# 5VDC_Supply.net
KiCad netlist of a schematic drawn in EAGLE
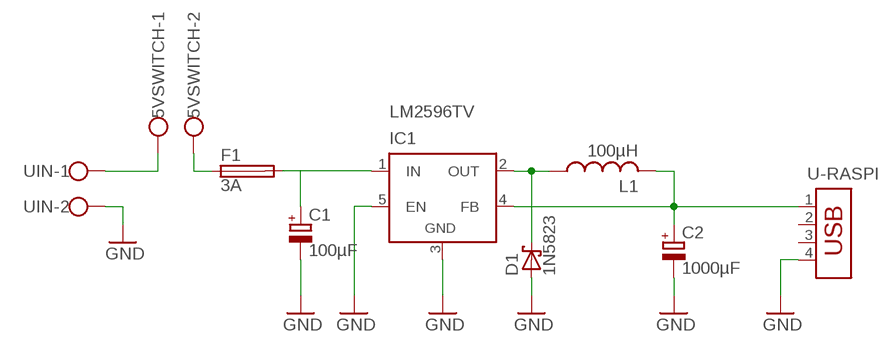
[diagram p0: schematic, sheet 1]

(export (version "E")
  (design (tool "Eeschema 10.0.6"))
  (components
    (comp (ref "5VSWITCH")
      (value "W237-102")
      (footprint "eagle-import:W237-102")
      (fields (field (name "MPN") "237-102"))
      (libsource (lib "eagle-import") (part "W237-102"))
    )
    (comp (ref "C1")
      (value "100µF")
      (footprint "eagle-import:E5-6")
      (libsource (lib "eagle-import") (part "CPOL-EUE5-6"))
    )
    (comp (ref "C2")
      (value "1000µF")
      (footprint "eagle-import:E5-10,5")
      (libsource (lib "eagle-import") (part "CPOL-EUE5-10.5"))
    )
    (comp (ref "D1")
      (value "1N5823")
      (footprint "eagle-import:C4111-15")
      (libsource (lib "eagle-import") (part "1N5908"))
    )
    (comp (ref "F1")
      (value "3A")
      (footprint "eagle-import:GSH15")
      (fields (field (name "MPN") "64900001039"))
      (libsource (lib "eagle-import") (part "GSH15"))
    )
    (comp (ref "IC1")
      (value "LM2596TV")
      (footprint "eagle-import:TO220-51")
      (libsource (lib "eagle-import") (part "LM2596TV"))
    )
    (comp (ref "L1")
      (value "100µH")
      (footprint "eagle-import:IRF-3")
      (libsource (lib "eagle-import") (part "L-USIRF-3"))
    )
    (comp (ref "U-RASPI")
      (value "USB-787616")
      (footprint "eagle-import:USB")
      (libsource (lib "eagle-import") (part "USB-787616"))
    )
    (comp (ref "UIN")
      (value "W237-102")
      (footprint "eagle-import:W237-102")
      (fields (field (name "MPN") "237-102"))
      (libsource (lib "eagle-import") (part "W237-102"))
    )
  )
  (nets
    (net (code "1") (name "GND") (class "Default")
      (node (ref "C1") (pin "-") (pinfunction "-_-") (pintype "passive"))
      (node (ref "C2") (pin "-") (pinfunction "-_-") (pintype "passive"))
      (node (ref "D1") (pin "A") (pinfunction "A_A") (pintype "passive"))
      (node (ref "IC1") (pin "3") (pinfunction "GND_3") (pintype "power_in"))
      (node (ref "IC1") (pin "5") (pinfunction "EN_5") (pintype "input"))
      (node (ref "U-RASPI") (pin "4") (pinfunction "4_4") (pintype "passive"))
      (node (ref "UIN") (pin "2") (pinfunction "KL_2") (pintype "passive"))
    )
    (net (code "2") (name "Net-(5VSWITCHA-KL)") (class "Default")
      (node (ref "5VSWITCH") (pin "1") (pinfunction "KL_1") (pintype "passive"))
      (node (ref "UIN") (pin "1") (pinfunction "KL_1") (pintype "passive"))
    )
    (net (code "3") (name "Net-(5VSWITCHB-KL)") (class "Default")
      (node (ref "5VSWITCH") (pin "2") (pinfunction "KL_2") (pintype "passive"))
      (node (ref "F1") (pin "1") (pinfunction "1_1") (pintype "passive"))
    )
    (net (code "4") (name "Net-(IC1-FB)") (class "Default")
      (node (ref "C2") (pin "+") (pinfunction "+_+") (pintype "passive"))
      (node (ref "IC1") (pin "4") (pinfunction "FB_4") (pintype "input"))
      (node (ref "L1") (pin "2") (pinfunction "2_2") (pintype "passive"))
      (node (ref "U-RASPI") (pin "1") (pinfunction "1_1") (pintype "passive"))
    )
    (net (code "5") (name "Net-(IC1-IN)") (class "Default")
      (node (ref "C1") (pin "+") (pinfunction "+_+") (pintype "passive"))
      (node (ref "F1") (pin "2") (pinfunction "2_2") (pintype "passive"))
      (node (ref "IC1") (pin "1") (pinfunction "IN_1") (pintype "input"))
    )
    (net (code "6") (name "Net-(IC1-OUT)") (class "Default")
      (node (ref "D1") (pin "C") (pinfunction "C_C") (pintype "passive"))
      (node (ref "IC1") (pin "2") (pinfunction "OUT_2") (pintype "output"))
      (node (ref "L1") (pin "1") (pinfunction "1_1") (pintype "passive"))
    )
    (net (code "7") (name "unconnected-(U-RASPI-Pad2)") (class "Default")
      (node (ref "U-RASPI") (pin "2") (pinfunction "2_2") (pintype "passive"))
    )
    (net (code "8") (name "unconnected-(U-RASPI-Pad3)") (class "Default")
      (node (ref "U-RASPI") (pin "3") (pinfunction "3_3") (pintype "passive"))
    )
  )
)
